# touch_controller.net
KiCad netlist of a schematic drawn in EAGLE
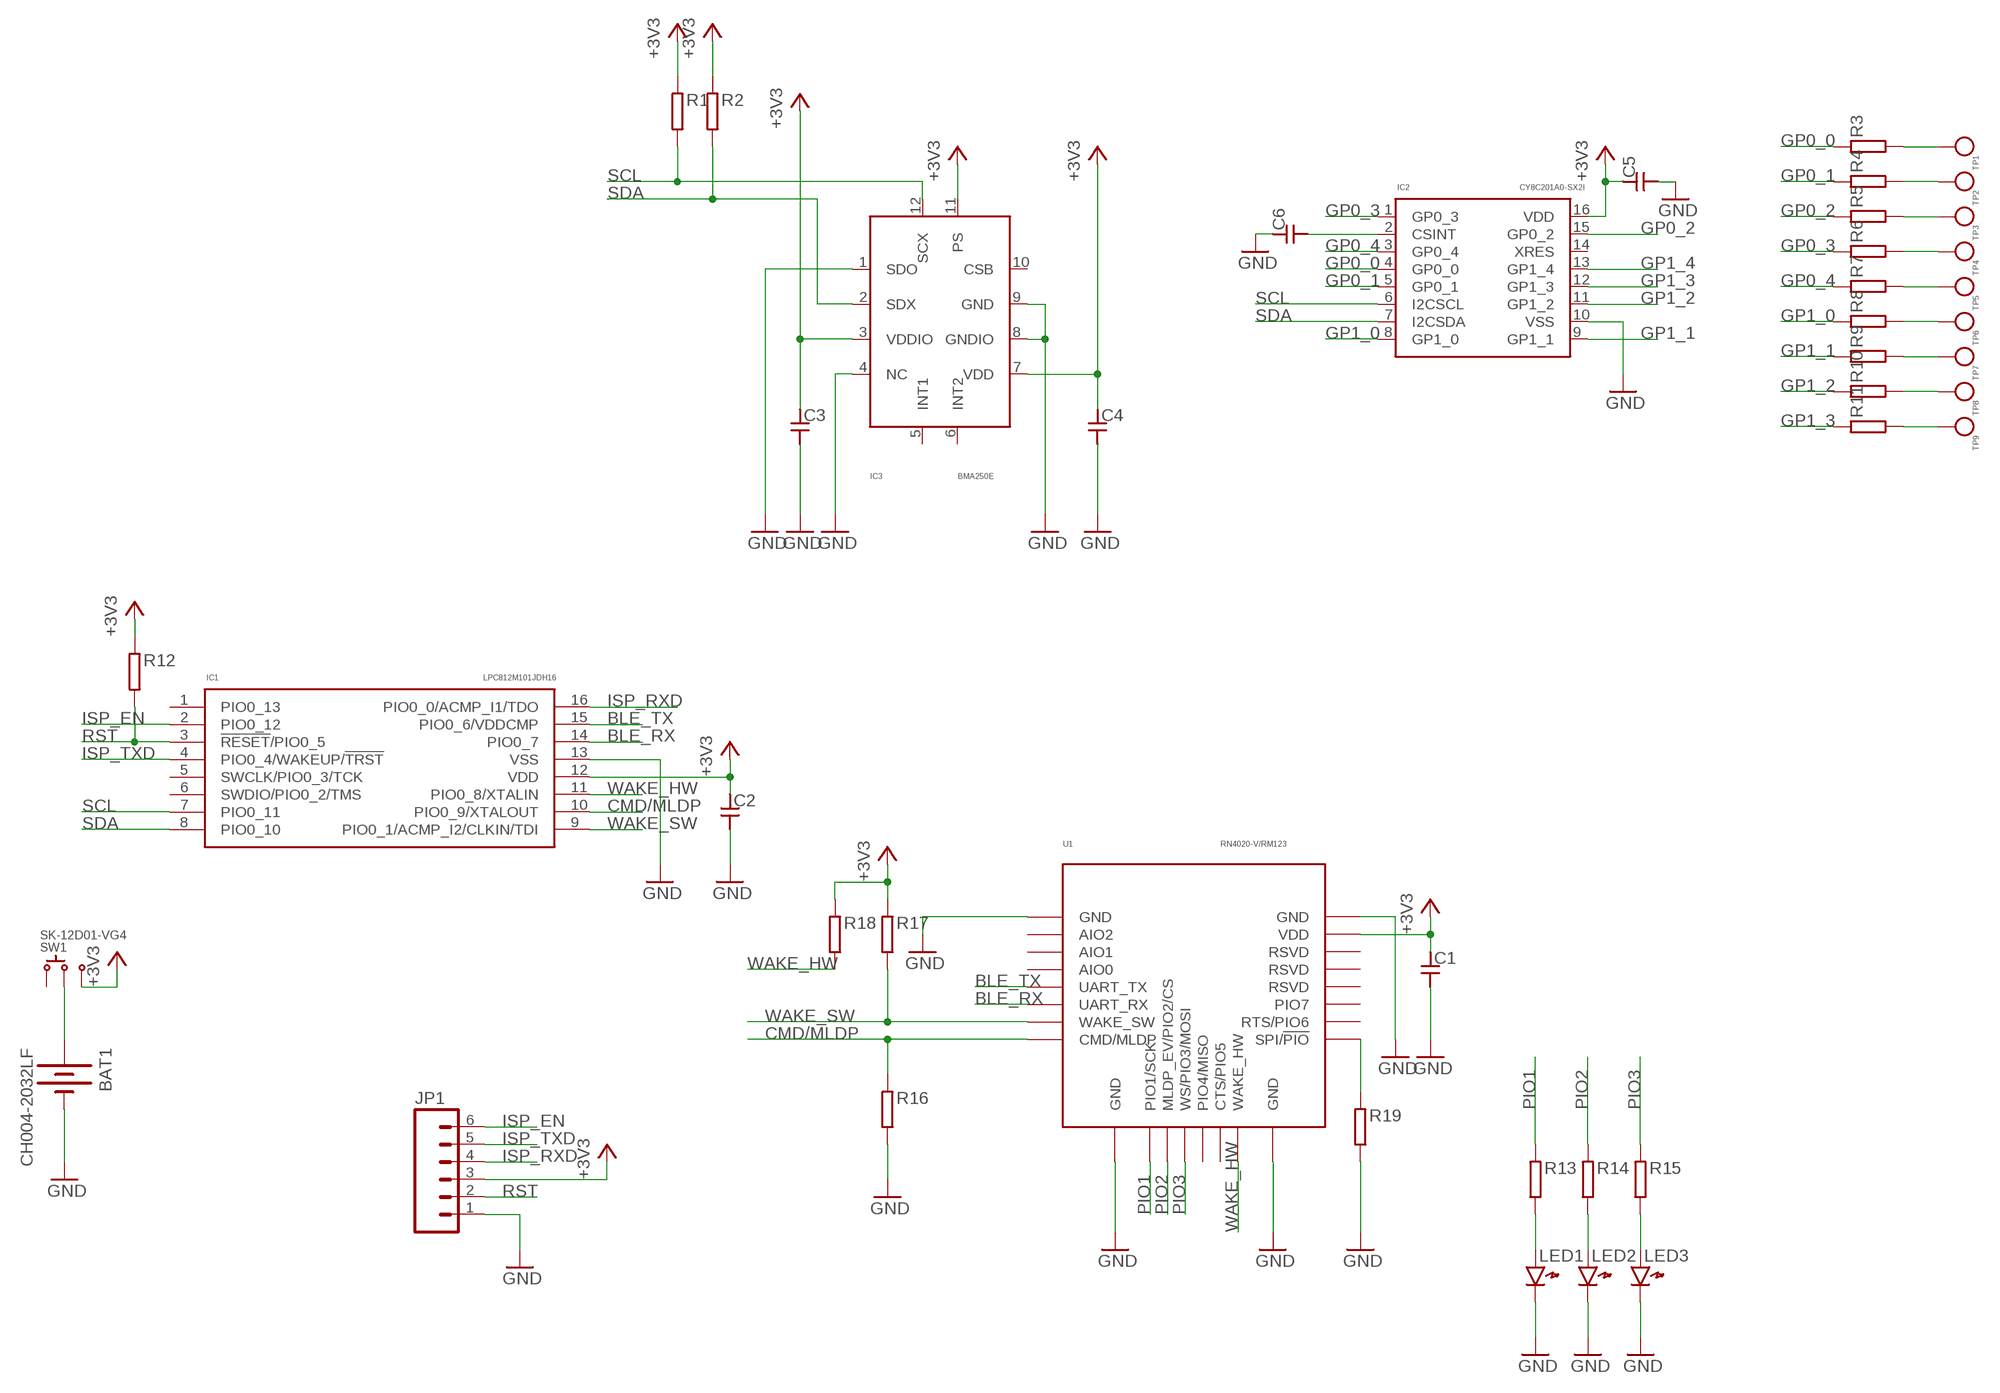
[diagram p0: schematic, sheet 1]

(export (version "E")
  (design (tool "Eeschema 10.0.6"))
  (components
    (comp (ref "BAT1")
      (value "CH004-2032LF")
      (footprint "eagle-import:CH004-2032LF")
      (libsource (lib "eagle-import") (part "CH004-2032LF"))
    )
    (comp (ref "C1")
      (value "CAPACITOR1608_REDUCED")
      (footprint "eagle-import:SMD1608_REDUCED")
      (libsource (lib "eagle-import") (part "CAPACITOR1608_REDUCED"))
    )
    (comp (ref "C2")
      (value "CAPACITOR1608_REDUCED")
      (footprint "eagle-import:SMD1608_REDUCED")
      (libsource (lib "eagle-import") (part "CAPACITOR1608_REDUCED"))
    )
    (comp (ref "C3")
      (value "CAPACITOR1608_REDUCED")
      (footprint "eagle-import:SMD1608_REDUCED")
      (libsource (lib "eagle-import") (part "CAPACITOR1608_REDUCED"))
    )
    (comp (ref "C4")
      (value "CAPACITOR1608_REDUCED")
      (footprint "eagle-import:SMD1608_REDUCED")
      (libsource (lib "eagle-import") (part "CAPACITOR1608_REDUCED"))
    )
    (comp (ref "C5")
      (value "CAPACITOR1608_REDUCED")
      (footprint "eagle-import:SMD1608_REDUCED")
      (libsource (lib "eagle-import") (part "CAPACITOR1608_REDUCED"))
    )
    (comp (ref "C6")
      (value "CAPACITOR1608_REDUCED")
      (footprint "eagle-import:SMD1608_REDUCED")
      (libsource (lib "eagle-import") (part "CAPACITOR1608_REDUCED"))
    )
    (comp (ref "IC1")
      (value "LPC812M101JDH16")
      (footprint "eagle-import:TSSOP16")
      (libsource (lib "eagle-import") (part "LPC812M101JDH16"))
    )
    (comp (ref "IC2")
      (value "CY8C201A0-SX2I")
      (footprint "eagle-import:SOIC-16")
      (libsource (lib "eagle-import") (part "CY8C201A0-SX2I"))
    )
    (comp (ref "IC3")
      (value "BMA250E")
      (footprint "eagle-import:LGA-12")
      (libsource (lib "eagle-import") (part "BMA250E"))
    )
    (comp (ref "JP1")
      (value "M06NOSILK")
      (footprint "eagle-import:1X06-NOSILK")
      (libsource (lib "eagle-import") (part "M06NOSILK"))
    )
    (comp (ref "LED1")
      (value "LED1608_REDUCED")
      (footprint "eagle-import:LED1608_REDUCED")
      (libsource (lib "eagle-import") (part "LED1608_REDUCED"))
    )
    (comp (ref "LED2")
      (value "LED1608_REDUCED")
      (footprint "eagle-import:LED1608_REDUCED")
      (libsource (lib "eagle-import") (part "LED1608_REDUCED"))
    )
    (comp (ref "LED3")
      (value "LED1608_REDUCED")
      (footprint "eagle-import:LED1608_REDUCED")
      (libsource (lib "eagle-import") (part "LED1608_REDUCED"))
    )
    (comp (ref "R1")
      (value "RESISTOR1608_REDUCED")
      (footprint "eagle-import:SMD1608_REDUCED")
      (libsource (lib "eagle-import") (part "RESISTOR1608_REDUCED"))
    )
    (comp (ref "R2")
      (value "RESISTOR1608_REDUCED")
      (footprint "eagle-import:SMD1608_REDUCED")
      (libsource (lib "eagle-import") (part "RESISTOR1608_REDUCED"))
    )
    (comp (ref "R3")
      (value "RESISTOR1608_REDUCED")
      (footprint "eagle-import:SMD1608_REDUCED")
      (libsource (lib "eagle-import") (part "RESISTOR1608_REDUCED"))
    )
    (comp (ref "R4")
      (value "RESISTOR1608_REDUCED")
      (footprint "eagle-import:SMD1608_REDUCED")
      (libsource (lib "eagle-import") (part "RESISTOR1608_REDUCED"))
    )
    (comp (ref "R5")
      (value "RESISTOR1608_REDUCED")
      (footprint "eagle-import:SMD1608_REDUCED")
      (libsource (lib "eagle-import") (part "RESISTOR1608_REDUCED"))
    )
    (comp (ref "R6")
      (value "RESISTOR1608_REDUCED")
      (footprint "eagle-import:SMD1608_REDUCED")
      (libsource (lib "eagle-import") (part "RESISTOR1608_REDUCED"))
    )
    (comp (ref "R7")
      (value "RESISTOR1608_REDUCED")
      (footprint "eagle-import:SMD1608_REDUCED")
      (libsource (lib "eagle-import") (part "RESISTOR1608_REDUCED"))
    )
    (comp (ref "R8")
      (value "RESISTOR1608_REDUCED")
      (footprint "eagle-import:SMD1608_REDUCED")
      (libsource (lib "eagle-import") (part "RESISTOR1608_REDUCED"))
    )
    (comp (ref "R9")
      (value "RESISTOR1608_REDUCED")
      (footprint "eagle-import:SMD1608_REDUCED")
      (libsource (lib "eagle-import") (part "RESISTOR1608_REDUCED"))
    )
    (comp (ref "R10")
      (value "RESISTOR1608_REDUCED")
      (footprint "eagle-import:SMD1608_REDUCED")
      (libsource (lib "eagle-import") (part "RESISTOR1608_REDUCED"))
    )
    (comp (ref "R11")
      (value "RESISTOR1608_REDUCED")
      (footprint "eagle-import:SMD1608_REDUCED")
      (libsource (lib "eagle-import") (part "RESISTOR1608_REDUCED"))
    )
    (comp (ref "R12")
      (value "RESISTOR1608_REDUCED")
      (footprint "eagle-import:SMD1608_REDUCED")
      (libsource (lib "eagle-import") (part "RESISTOR1608_REDUCED"))
    )
    (comp (ref "R13")
      (value "RESISTOR1608_REDUCED")
      (footprint "eagle-import:SMD1608_REDUCED")
      (libsource (lib "eagle-import") (part "RESISTOR1608_REDUCED"))
    )
    (comp (ref "R14")
      (value "RESISTOR1608_REDUCED")
      (footprint "eagle-import:SMD1608_REDUCED")
      (libsource (lib "eagle-import") (part "RESISTOR1608_REDUCED"))
    )
    (comp (ref "R15")
      (value "RESISTOR1608_REDUCED")
      (footprint "eagle-import:SMD1608_REDUCED")
      (libsource (lib "eagle-import") (part "RESISTOR1608_REDUCED"))
    )
    (comp (ref "R16")
      (value "RESISTOR1608_REDUCED")
      (footprint "eagle-import:SMD1608_REDUCED")
      (libsource (lib "eagle-import") (part "RESISTOR1608_REDUCED"))
    )
    (comp (ref "R17")
      (value "RESISTOR1608_REDUCED")
      (footprint "eagle-import:SMD1608_REDUCED")
      (libsource (lib "eagle-import") (part "RESISTOR1608_REDUCED"))
    )
    (comp (ref "R18")
      (value "RESISTOR1608_REDUCED")
      (footprint "eagle-import:SMD1608_REDUCED")
      (libsource (lib "eagle-import") (part "RESISTOR1608_REDUCED"))
    )
    (comp (ref "R19")
      (value "RESISTOR1608_REDUCED")
      (footprint "eagle-import:SMD1608_REDUCED")
      (libsource (lib "eagle-import") (part "RESISTOR1608_REDUCED"))
    )
    (comp (ref "SW1")
      (value "SK-12D01-VG4")
      (footprint "eagle-import:SK-12D01-VG4")
      (libsource (lib "eagle-import") (part "SK-12D01-VG4"))
    )
    (comp (ref "TP1")
      (value "HT-0720-10")
      (footprint "eagle-import:HT-0720-10")
      (libsource (lib "eagle-import") (part "HT-0720-10"))
    )
    (comp (ref "TP2")
      (value "HT-0720-10")
      (footprint "eagle-import:HT-0720-10")
      (libsource (lib "eagle-import") (part "HT-0720-10"))
    )
    (comp (ref "TP3")
      (value "HT-0720-10")
      (footprint "eagle-import:HT-0720-10")
      (libsource (lib "eagle-import") (part "HT-0720-10"))
    )
    (comp (ref "TP4")
      (value "HT-0720-10")
      (footprint "eagle-import:HT-0720-10")
      (libsource (lib "eagle-import") (part "HT-0720-10"))
    )
    (comp (ref "TP5")
      (value "HT-0720-10")
      (footprint "eagle-import:HT-0720-10")
      (libsource (lib "eagle-import") (part "HT-0720-10"))
    )
    (comp (ref "TP6")
      (value "HT-0720-10")
      (footprint "eagle-import:HT-0720-10")
      (libsource (lib "eagle-import") (part "HT-0720-10"))
    )
    (comp (ref "TP7")
      (value "HT-0720-10")
      (footprint "eagle-import:HT-0720-10")
      (libsource (lib "eagle-import") (part "HT-0720-10"))
    )
    (comp (ref "TP8")
      (value "HT-0720-10")
      (footprint "eagle-import:HT-0720-10")
      (libsource (lib "eagle-import") (part "HT-0720-10"))
    )
    (comp (ref "TP9")
      (value "HT-0720-10")
      (footprint "eagle-import:HT-0720-10")
      (libsource (lib "eagle-import") (part "HT-0720-10"))
    )
    (comp (ref "U1")
      (value "RN4020-V/RM123")
      (footprint "eagle-import:RN4020")
      (libsource (lib "eagle-import") (part "RN4020-V/RM123"))
    )
  )
  (nets
    (net (code "1") (name "+3V3") (class "Default")
      (node (ref "C1") (pin "1") (pinfunction "1_1") (pintype "passive"))
      (node (ref "C2") (pin "1") (pinfunction "1_1") (pintype "passive"))
      (node (ref "C3") (pin "1") (pinfunction "1_1") (pintype "passive"))
      (node (ref "C4") (pin "1") (pinfunction "1_1") (pintype "passive"))
      (node (ref "C5") (pin "1") (pinfunction "1_1") (pintype "passive"))
      (node (ref "IC1") (pin "12") (pinfunction "VDD_12") (pintype "bidirectional"))
      (node (ref "IC2") (pin "16") (pinfunction "VDD_16") (pintype "bidirectional"))
      (node (ref "IC3") (pin "11") (pinfunction "PS_11") (pintype "bidirectional"))
      (node (ref "IC3") (pin "3") (pinfunction "VDDIO_3") (pintype "bidirectional"))
      (node (ref "IC3") (pin "7") (pinfunction "VDD_7") (pintype "bidirectional"))
      (node (ref "JP1") (pin "3") (pinfunction "3_3") (pintype "passive"))
      (node (ref "R1") (pin "1") (pinfunction "1_1") (pintype "passive"))
      (node (ref "R12") (pin "1") (pinfunction "1_1") (pintype "passive"))
      (node (ref "R17") (pin "1") (pinfunction "1_1") (pintype "passive"))
      (node (ref "R18") (pin "1") (pinfunction "1_1") (pintype "passive"))
      (node (ref "R2") (pin "1") (pinfunction "1_1") (pintype "passive"))
      (node (ref "SW1") (pin "3") (pinfunction "P$3_3") (pintype "bidirectional"))
      (node (ref "U1") (pin "23") (pinfunction "VDD_23") (pintype "bidirectional"))
    )
    (net (code "2") (name "/BLE_RX") (class "Default")
      (node (ref "IC1") (pin "14") (pinfunction "PIO0_7_14") (pintype "bidirectional"))
      (node (ref "U1") (pin "6") (pinfunction "UART_RX_6") (pintype "bidirectional"))
    )
    (net (code "3") (name "/BLE_TX") (class "Default")
      (node (ref "IC1") (pin "15") (pinfunction "PIO0_6/VDDCMP_15") (pintype "bidirectional"))
      (node (ref "U1") (pin "5") (pinfunction "UART_TX_5") (pintype "bidirectional"))
    )
    (net (code "4") (name "/CMD{slash}MLDP") (class "Default")
      (node (ref "IC1") (pin "10") (pinfunction "PIO0_9/XTALOUT_10") (pintype "bidirectional"))
      (node (ref "R16") (pin "1") (pinfunction "1_1") (pintype "passive"))
      (node (ref "U1") (pin "8") (pinfunction "CMD/MLDP_8") (pintype "bidirectional"))
    )
    (net (code "5") (name "/GP0_0") (class "Default")
      (node (ref "IC2") (pin "4") (pinfunction "GP0_0_4") (pintype "bidirectional"))
      (node (ref "R3") (pin "1") (pinfunction "1_1") (pintype "passive"))
    )
    (net (code "6") (name "/GP0_1") (class "Default")
      (node (ref "IC2") (pin "5") (pinfunction "GP0_1_5") (pintype "bidirectional"))
      (node (ref "R4") (pin "1") (pinfunction "1_1") (pintype "passive"))
    )
    (net (code "7") (name "/GP0_2") (class "Default")
      (node (ref "IC2") (pin "15") (pinfunction "GP0_2_15") (pintype "bidirectional"))
      (node (ref "R5") (pin "1") (pinfunction "1_1") (pintype "passive"))
    )
    (net (code "8") (name "/GP0_3") (class "Default")
      (node (ref "IC2") (pin "1") (pinfunction "GP0_3_1") (pintype "bidirectional"))
      (node (ref "R6") (pin "1") (pinfunction "1_1") (pintype "passive"))
    )
    (net (code "9") (name "/GP0_4") (class "Default")
      (node (ref "IC2") (pin "3") (pinfunction "GP0_4_3") (pintype "bidirectional"))
      (node (ref "R7") (pin "1") (pinfunction "1_1") (pintype "passive"))
    )
    (net (code "10") (name "/GP1_0") (class "Default")
      (node (ref "IC2") (pin "8") (pinfunction "GP1_0_8") (pintype "bidirectional"))
      (node (ref "R8") (pin "1") (pinfunction "1_1") (pintype "passive"))
    )
    (net (code "11") (name "/GP1_1") (class "Default")
      (node (ref "IC2") (pin "9") (pinfunction "GP1_1_9") (pintype "bidirectional"))
      (node (ref "R9") (pin "1") (pinfunction "1_1") (pintype "passive"))
    )
    (net (code "12") (name "/GP1_2") (class "Default")
      (node (ref "IC2") (pin "11") (pinfunction "GP1_2_11") (pintype "bidirectional"))
      (node (ref "R10") (pin "1") (pinfunction "1_1") (pintype "passive"))
    )
    (net (code "13") (name "/GP1_3") (class "Default")
      (node (ref "IC2") (pin "12") (pinfunction "GP1_3_12") (pintype "bidirectional"))
      (node (ref "R11") (pin "1") (pinfunction "1_1") (pintype "passive"))
    )
    (net (code "14") (name "/GP1_4") (class "Default")
      (node (ref "IC2") (pin "13") (pinfunction "GP1_4_13") (pintype "bidirectional"))
    )
    (net (code "15") (name "/ISP_EN") (class "Default")
      (node (ref "IC1") (pin "2") (pinfunction "PIO0_12_2") (pintype "bidirectional"))
      (node (ref "JP1") (pin "6") (pinfunction "6_6") (pintype "passive"))
    )
    (net (code "16") (name "/ISP_RXD") (class "Default")
      (node (ref "IC1") (pin "16") (pinfunction "PIO0_0/ACMP_I1/TDO_16") (pintype "bidirectional"))
      (node (ref "JP1") (pin "4") (pinfunction "4_4") (pintype "passive"))
    )
    (net (code "17") (name "/ISP_TXD") (class "Default")
      (node (ref "IC1") (pin "4") (pinfunction "PIO0_4/WAKEUP/~{TRST}_4") (pintype "bidirectional"))
      (node (ref "JP1") (pin "5") (pinfunction "5_5") (pintype "passive"))
    )
    (net (code "18") (name "/PIO1") (class "Default")
      (node (ref "R13") (pin "1") (pinfunction "1_1") (pintype "passive"))
      (node (ref "U1") (pin "10") (pinfunction "PIO1/SCK_10") (pintype "bidirectional"))
    )
    (net (code "19") (name "/PIO2") (class "Default")
      (node (ref "R14") (pin "1") (pinfunction "1_1") (pintype "passive"))
      (node (ref "U1") (pin "11") (pinfunction "MLDP_EV/PIO2/CS_11") (pintype "bidirectional"))
    )
    (net (code "20") (name "/PIO3") (class "Default")
      (node (ref "R15") (pin "1") (pinfunction "1_1") (pintype "passive"))
      (node (ref "U1") (pin "12") (pinfunction "WS/PIO3/MOSI_12") (pintype "bidirectional"))
    )
    (net (code "21") (name "/RST") (class "Default")
      (node (ref "IC1") (pin "3") (pinfunction "~{RESET}/PIO0_5_3") (pintype "bidirectional"))
      (node (ref "JP1") (pin "2") (pinfunction "2_2") (pintype "passive"))
      (node (ref "R12") (pin "2") (pinfunction "2_2") (pintype "passive"))
    )
    (net (code "22") (name "/SCL") (class "Default")
      (node (ref "IC1") (pin "7") (pinfunction "PIO0_11_7") (pintype "bidirectional"))
      (node (ref "IC2") (pin "6") (pinfunction "I2CSCL_6") (pintype "bidirectional"))
      (node (ref "IC3") (pin "12") (pinfunction "SCX_12") (pintype "bidirectional"))
      (node (ref "R1") (pin "2") (pinfunction "2_2") (pintype "passive"))
    )
    (net (code "23") (name "/SDA") (class "Default")
      (node (ref "IC1") (pin "8") (pinfunction "PIO0_10_8") (pintype "bidirectional"))
      (node (ref "IC2") (pin "7") (pinfunction "I2CSDA_7") (pintype "bidirectional"))
      (node (ref "IC3") (pin "2") (pinfunction "SDX_2") (pintype "bidirectional"))
      (node (ref "R2") (pin "2") (pinfunction "2_2") (pintype "passive"))
    )
    (net (code "24") (name "/WAKE_HW") (class "Default")
      (node (ref "IC1") (pin "11") (pinfunction "PIO0_8/XTALIN_11") (pintype "bidirectional"))
      (node (ref "R18") (pin "2") (pinfunction "2_2") (pintype "passive"))
      (node (ref "U1") (pin "15") (pinfunction "WAKE_HW_15") (pintype "bidirectional"))
    )
    (net (code "25") (name "/WAKE_SW") (class "Default")
      (node (ref "IC1") (pin "9") (pinfunction "PIO0_1/ACMP_I2/CLKIN/TDI_9") (pintype "bidirectional"))
      (node (ref "R17") (pin "2") (pinfunction "2_2") (pintype "passive"))
      (node (ref "U1") (pin "7") (pinfunction "WAKE_SW_7") (pintype "bidirectional"))
    )
    (net (code "26") (name "GND") (class "Default")
      (node (ref "BAT1") (pin "-") (pinfunction "-_-") (pintype "power_in"))
      (node (ref "C1") (pin "2") (pinfunction "2_2") (pintype "passive"))
      (node (ref "C2") (pin "2") (pinfunction "2_2") (pintype "passive"))
      (node (ref "C3") (pin "2") (pinfunction "2_2") (pintype "passive"))
      (node (ref "C4") (pin "2") (pinfunction "2_2") (pintype "passive"))
      (node (ref "C5") (pin "2") (pinfunction "2_2") (pintype "passive"))
      (node (ref "C6") (pin "1") (pinfunction "1_1") (pintype "passive"))
      (node (ref "IC1") (pin "13") (pinfunction "VSS_13") (pintype "bidirectional"))
      (node (ref "IC2") (pin "10") (pinfunction "VSS_10") (pintype "bidirectional"))
      (node (ref "IC3") (pin "1") (pinfunction "SDO_1") (pintype "bidirectional"))
      (node (ref "IC3") (pin "4") (pinfunction "NC_4") (pintype "bidirectional"))
      (node (ref "IC3") (pin "8") (pinfunction "GNDIO_8") (pintype "bidirectional"))
      (node (ref "IC3") (pin "9") (pinfunction "GND_9") (pintype "bidirectional"))
      (node (ref "JP1") (pin "1") (pinfunction "1_1") (pintype "passive"))
      (node (ref "LED1") (pin "K") (pinfunction "K_K") (pintype "passive"))
      (node (ref "LED2") (pin "K") (pinfunction "K_K") (pintype "passive"))
      (node (ref "LED3") (pin "K") (pinfunction "K_K") (pintype "passive"))
      (node (ref "R16") (pin "2") (pinfunction "2_2") (pintype "passive"))
      (node (ref "R19") (pin "2") (pinfunction "2_2") (pintype "passive"))
      (node (ref "U1") (pin "1") (pinfunction "GND_1") (pintype "bidirectional"))
      (node (ref "U1") (pin "16") (pinfunction "GND_16") (pintype "bidirectional"))
      (node (ref "U1") (pin "24") (pinfunction "GND_24") (pintype "bidirectional"))
      (node (ref "U1") (pin "9") (pinfunction "GND_9") (pintype "bidirectional"))
    )
    (net (code "27") (name "Net-(IC2-CSINT)") (class "Default")
      (node (ref "C6") (pin "2") (pinfunction "2_2") (pintype "passive"))
      (node (ref "IC2") (pin "2") (pinfunction "CSINT_2") (pintype "bidirectional"))
    )
    (net (code "28") (name "Net-(LED1-PadA)") (class "Default")
      (node (ref "LED1") (pin "A") (pinfunction "A_A") (pintype "passive"))
      (node (ref "R13") (pin "2") (pinfunction "2_2") (pintype "passive"))
    )
    (net (code "29") (name "Net-(LED2-PadA)") (class "Default")
      (node (ref "LED2") (pin "A") (pinfunction "A_A") (pintype "passive"))
      (node (ref "R14") (pin "2") (pinfunction "2_2") (pintype "passive"))
    )
    (net (code "30") (name "Net-(LED3-PadA)") (class "Default")
      (node (ref "LED3") (pin "A") (pinfunction "A_A") (pintype "passive"))
      (node (ref "R15") (pin "2") (pinfunction "2_2") (pintype "passive"))
    )
    (net (code "31") (name "Net-(R3-Pad2)") (class "Default")
      (node (ref "R3") (pin "2") (pinfunction "2_2") (pintype "passive"))
      (node (ref "TP1") (pin "P$1") (pinfunction "P$1_P$1") (pintype "bidirectional"))
    )
    (net (code "32") (name "Net-(R4-Pad2)") (class "Default")
      (node (ref "R4") (pin "2") (pinfunction "2_2") (pintype "passive"))
      (node (ref "TP2") (pin "P$1") (pinfunction "P$1_P$1") (pintype "bidirectional"))
    )
    (net (code "33") (name "Net-(R5-Pad2)") (class "Default")
      (node (ref "R5") (pin "2") (pinfunction "2_2") (pintype "passive"))
      (node (ref "TP3") (pin "P$1") (pinfunction "P$1_P$1") (pintype "bidirectional"))
    )
    (net (code "34") (name "Net-(R6-Pad2)") (class "Default")
      (node (ref "R6") (pin "2") (pinfunction "2_2") (pintype "passive"))
      (node (ref "TP4") (pin "P$1") (pinfunction "P$1_P$1") (pintype "bidirectional"))
    )
    (net (code "35") (name "Net-(R7-Pad2)") (class "Default")
      (node (ref "R7") (pin "2") (pinfunction "2_2") (pintype "passive"))
      (node (ref "TP5") (pin "P$1") (pinfunction "P$1_P$1") (pintype "bidirectional"))
    )
    (net (code "36") (name "Net-(R8-Pad2)") (class "Default")
      (node (ref "R8") (pin "2") (pinfunction "2_2") (pintype "passive"))
      (node (ref "TP6") (pin "P$1") (pinfunction "P$1_P$1") (pintype "bidirectional"))
    )
    (net (code "37") (name "Net-(R9-Pad2)") (class "Default")
      (node (ref "R9") (pin "2") (pinfunction "2_2") (pintype "passive"))
      (node (ref "TP7") (pin "P$1") (pinfunction "P$1_P$1") (pintype "bidirectional"))
    )
    (net (code "38") (name "Net-(R10-Pad2)") (class "Default")
      (node (ref "R10") (pin "2") (pinfunction "2_2") (pintype "passive"))
      (node (ref "TP8") (pin "P$1") (pinfunction "P$1_P$1") (pintype "bidirectional"))
    )
    (net (code "39") (name "Net-(R11-Pad2)") (class "Default")
      (node (ref "R11") (pin "2") (pinfunction "2_2") (pintype "passive"))
      (node (ref "TP9") (pin "P$1") (pinfunction "P$1_P$1") (pintype "bidirectional"))
    )
    (net (code "40") (name "Net-(SW1-P$2)") (class "Default")
      (node (ref "BAT1") (pin "+") (pinfunction "+_+") (pintype "power_in"))
      (node (ref "SW1") (pin "2") (pinfunction "P$2_2") (pintype "bidirectional"))
    )
    (net (code "41") (name "Net-(U1-SPI{slash}~{PIO})") (class "Default")
      (node (ref "R19") (pin "1") (pinfunction "1_1") (pintype "passive"))
      (node (ref "U1") (pin "17") (pinfunction "SPI/~{PIO}_17") (pintype "bidirectional"))
    )
    (net (code "42") (name "unconnected-(IC1-PIO0_13-Pad1)") (class "Default")
      (node (ref "IC1") (pin "1") (pinfunction "PIO0_13_1") (pintype "bidirectional"))
    )
    (net (code "43") (name "unconnected-(IC1-SWCLK{slash}PIO0_3{slash}TCK-Pad5)") (class "Default")
      (node (ref "IC1") (pin "5") (pinfunction "SWCLK/PIO0_3/TCK_5") (pintype "bidirectional"))
    )
    (net (code "44") (name "unconnected-(IC1-SWDIO{slash}PIO0_2{slash}TMS-Pad6)") (class "Default")
      (node (ref "IC1") (pin "6") (pinfunction "SWDIO/PIO0_2/TMS_6") (pintype "bidirectional"))
    )
    (net (code "45") (name "unconnected-(IC2-XRES-Pad14)") (class "Default")
      (node (ref "IC2") (pin "14") (pinfunction "XRES_14") (pintype "bidirectional"))
    )
    (net (code "46") (name "unconnected-(IC3-CSB-Pad10)") (class "Default")
      (node (ref "IC3") (pin "10") (pinfunction "CSB_10") (pintype "bidirectional"))
    )
    (net (code "47") (name "unconnected-(IC3-INT1-Pad5)") (class "Default")
      (node (ref "IC3") (pin "5") (pinfunction "INT1_5") (pintype "bidirectional"))
    )
    (net (code "48") (name "unconnected-(IC3-INT2-Pad6)") (class "Default")
      (node (ref "IC3") (pin "6") (pinfunction "INT2_6") (pintype "bidirectional"))
    )
    (net (code "49") (name "unconnected-(SW1-P$1-Pad1)") (class "Default")
      (node (ref "SW1") (pin "1") (pinfunction "P$1_1") (pintype "bidirectional"))
    )
    (net (code "50") (name "unconnected-(U1-AIO0-Pad4)") (class "Default")
      (node (ref "U1") (pin "4") (pinfunction "AIO0_4") (pintype "bidirectional"))
    )
    (net (code "51") (name "unconnected-(U1-AIO1-Pad3)") (class "Default")
      (node (ref "U1") (pin "3") (pinfunction "AIO1_3") (pintype "bidirectional"))
    )
    (net (code "52") (name "unconnected-(U1-AIO2-Pad2)") (class "Default")
      (node (ref "U1") (pin "2") (pinfunction "AIO2_2") (pintype "bidirectional"))
    )
    (net (code "53") (name "unconnected-(U1-CTS{slash}PIO5-Pad14)") (class "Default")
      (node (ref "U1") (pin "14") (pinfunction "CTS/PIO5_14") (pintype "bidirectional"))
    )
    (net (code "54") (name "unconnected-(U1-PIO4{slash}MISO-Pad13)") (class "Default")
      (node (ref "U1") (pin "13") (pinfunction "PIO4/MISO_13") (pintype "bidirectional"))
    )
    (net (code "55") (name "unconnected-(U1-PIO7-Pad19)") (class "Default")
      (node (ref "U1") (pin "19") (pinfunction "PIO7_19") (pintype "bidirectional"))
    )
    (net (code "56") (name "unconnected-(U1-RSVD-Pad20)") (class "Default")
      (node (ref "U1") (pin "20") (pinfunction "RSVD_20") (pintype "bidirectional"))
    )
    (net (code "57") (name "unconnected-(U1-RSVD-Pad21)") (class "Default")
      (node (ref "U1") (pin "21") (pinfunction "RSVD_21") (pintype "bidirectional"))
    )
    (net (code "58") (name "unconnected-(U1-RSVD-Pad22)") (class "Default")
      (node (ref "U1") (pin "22") (pinfunction "RSVD_22") (pintype "bidirectional"))
    )
    (net (code "59") (name "unconnected-(U1-RTS{slash}PIO6-Pad18)") (class "Default")
      (node (ref "U1") (pin "18") (pinfunction "RTS/PIO6_18") (pintype "bidirectional"))
    )
  )
)
